# Arduino_ultrasonic_triac.net
KiCad netlist of a schematic drawn in EAGLE
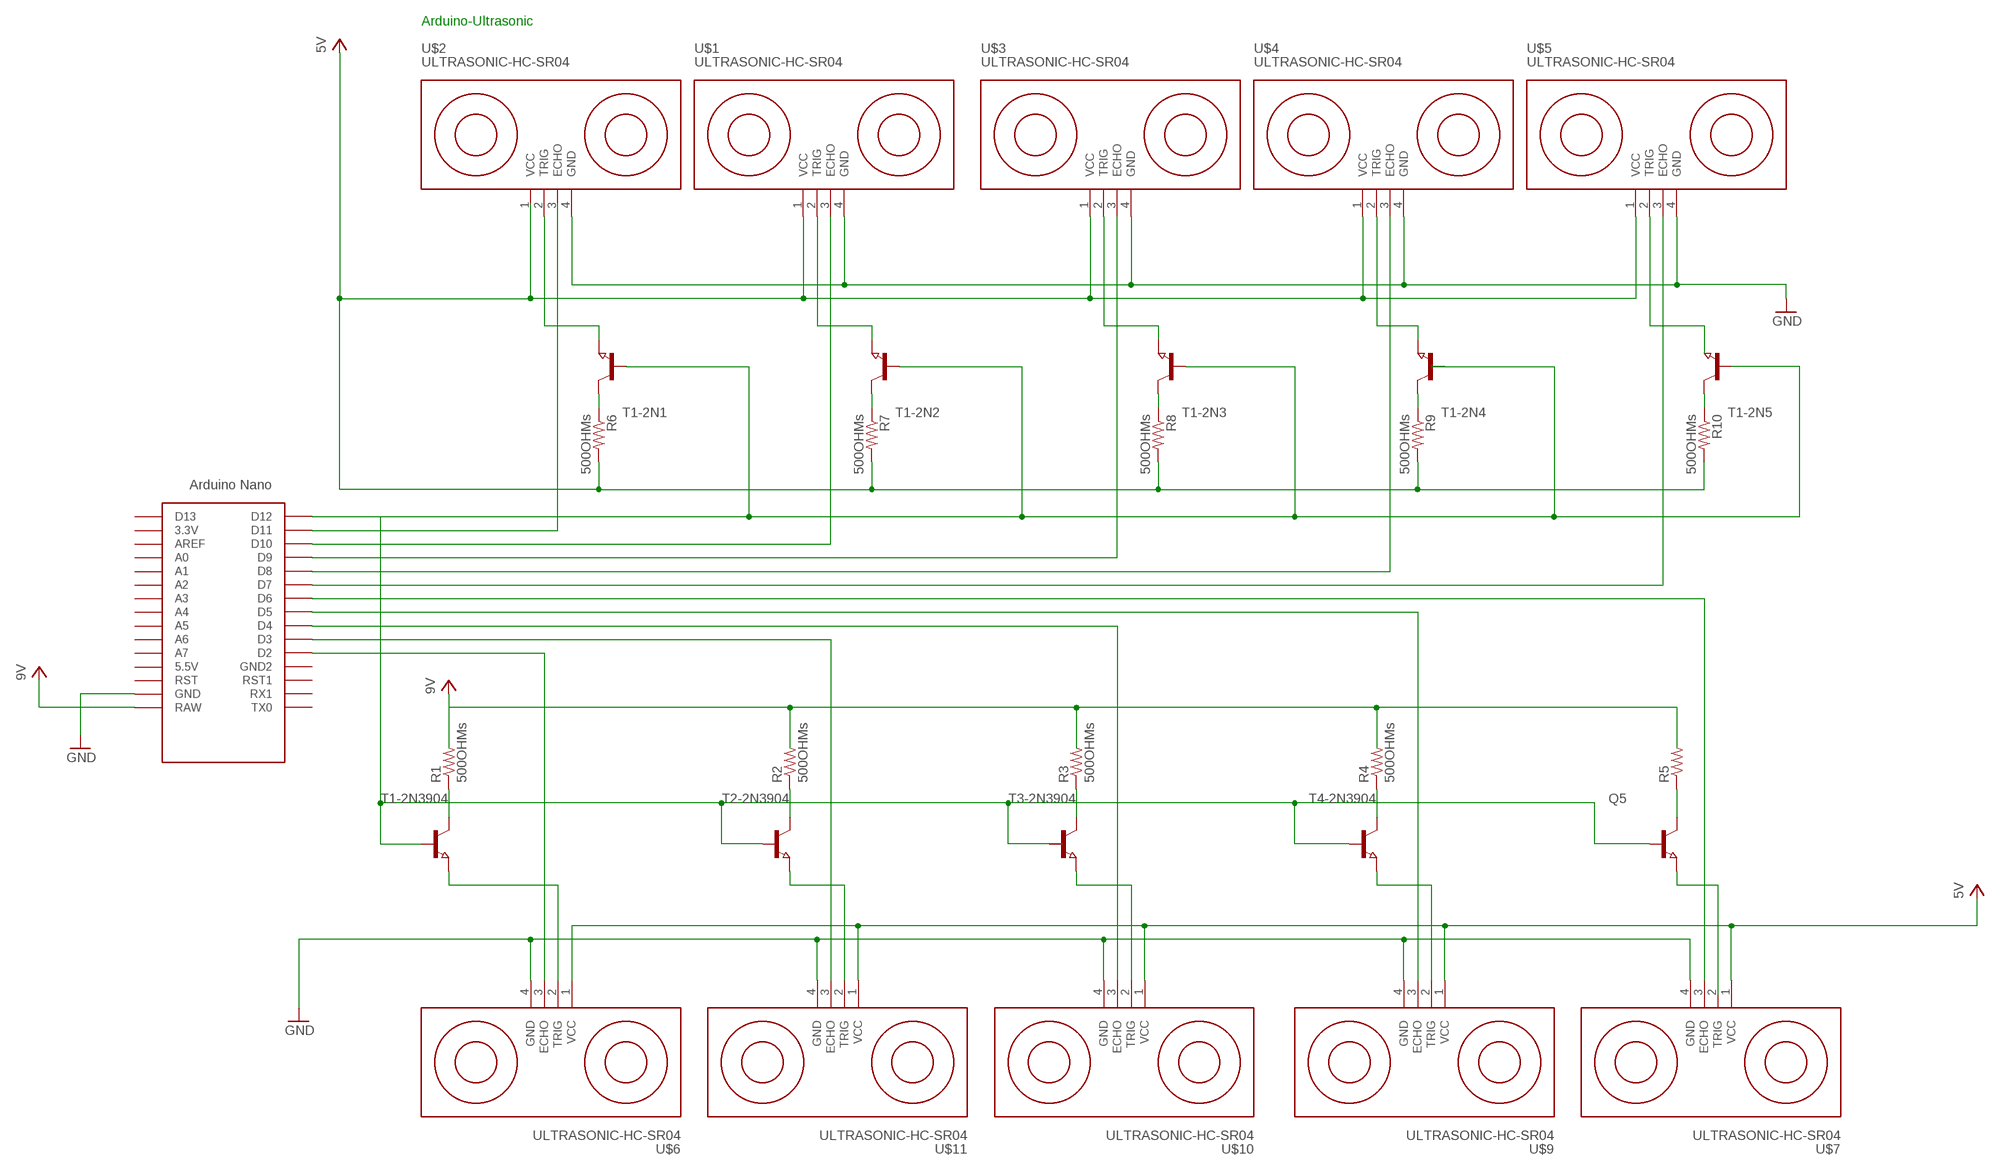
[diagram p0: schematic, sheet 1]

(export (version "E")
  (design (tool "Eeschema 10.0.6"))
  (components
    (comp (ref "Q5")
      (value "NPN-TRANSISTOR_SOT23")
      (footprint "eagle-import:SOT23")
      (libsource (lib "eagle-import") (part "NPN-TRANSISTOR_SOT23"))
    )
    (comp (ref "R1")
      (value "500OHMs")
      (footprint "eagle-import:0204V")
      (libsource (lib "eagle-import") (part "R-US_0204/2V"))
    )
    (comp (ref "R2")
      (value "500OHMs")
      (footprint "eagle-import:0204V")
      (libsource (lib "eagle-import") (part "R-US_0204/2V"))
    )
    (comp (ref "R3")
      (value "500OHMs")
      (footprint "eagle-import:0204V")
      (libsource (lib "eagle-import") (part "R-US_0204/2V"))
    )
    (comp (ref "R4")
      (value "500OHMs")
      (footprint "eagle-import:0204V")
      (libsource (lib "eagle-import") (part "R-US_0204/2V"))
    )
    (comp (ref "R5")
      (value "R-US_0204/2V")
      (footprint "eagle-import:0204V")
      (libsource (lib "eagle-import") (part "R-US_0204/2V"))
    )
    (comp (ref "R6")
      (value "500OHMs")
      (footprint "eagle-import:0204V")
      (libsource (lib "eagle-import") (part "R-US_0204/2V"))
    )
    (comp (ref "R7")
      (value "500OHMs")
      (footprint "eagle-import:0204V")
      (libsource (lib "eagle-import") (part "R-US_0204/2V"))
    )
    (comp (ref "R8")
      (value "500OHMs")
      (footprint "eagle-import:0204V")
      (libsource (lib "eagle-import") (part "R-US_0204/2V"))
    )
    (comp (ref "R9")
      (value "500OHMs")
      (footprint "eagle-import:0204V")
      (libsource (lib "eagle-import") (part "R-US_0204/2V"))
    )
    (comp (ref "R10")
      (value "500OHMs")
      (footprint "eagle-import:0204V")
      (libsource (lib "eagle-import") (part "R-US_0204/2V"))
    )
    (comp (ref "T1-2N1")
      (value "NPN-TRANSISTOR_SOT23")
      (footprint "eagle-import:SOT23")
      (libsource (lib "eagle-import") (part "NPN-TRANSISTOR_SOT23"))
    )
    (comp (ref "T1-2N2")
      (value "NPN-TRANSISTOR_SOT23")
      (footprint "eagle-import:SOT23")
      (libsource (lib "eagle-import") (part "NPN-TRANSISTOR_SOT23"))
    )
    (comp (ref "T1-2N3")
      (value "NPN-TRANSISTOR_SOT23")
      (footprint "eagle-import:SOT23")
      (libsource (lib "eagle-import") (part "NPN-TRANSISTOR_SOT23"))
    )
    (comp (ref "T1-2N4")
      (value "NPN-TRANSISTOR_SOT23")
      (footprint "eagle-import:SOT23")
      (libsource (lib "eagle-import") (part "NPN-TRANSISTOR_SOT23"))
    )
    (comp (ref "T1-2N5")
      (value "NPN-TRANSISTOR_SOT23")
      (footprint "eagle-import:SOT23")
      (libsource (lib "eagle-import") (part "NPN-TRANSISTOR_SOT23"))
    )
    (comp (ref "T1-2N3904")
      (value "NPN-TRANSISTOR_SOT23")
      (footprint "eagle-import:SOT23")
      (libsource (lib "eagle-import") (part "NPN-TRANSISTOR_SOT23"))
    )
    (comp (ref "T2-2N3904")
      (value "NPN-TRANSISTOR_SOT23")
      (footprint "eagle-import:SOT23")
      (libsource (lib "eagle-import") (part "NPN-TRANSISTOR_SOT23"))
    )
    (comp (ref "T3-2N3904")
      (value "NPN-TRANSISTOR_SOT23")
      (footprint "eagle-import:SOT23")
      (libsource (lib "eagle-import") (part "NPN-TRANSISTOR_SOT23"))
    )
    (comp (ref "T4-2N3904")
      (value "NPN-TRANSISTOR_SOT23")
      (footprint "eagle-import:SOT23")
      (libsource (lib "eagle-import") (part "NPN-TRANSISTOR_SOT23"))
    )
    (comp (ref "U$1")
      (value "ULTRASONIC-HC-SR04")
      (footprint "eagle-import:ULTRASONIC-HC-SR04")
      (libsource (lib "eagle-import") (part "ULTRASONIC-HC-SR04"))
    )
    (comp (ref "U$2")
      (value "ULTRASONIC-HC-SR04")
      (footprint "eagle-import:ULTRASONIC-HC-SR04")
      (libsource (lib "eagle-import") (part "ULTRASONIC-HC-SR04"))
    )
    (comp (ref "U$3")
      (value "ULTRASONIC-HC-SR04")
      (footprint "eagle-import:ULTRASONIC-HC-SR04")
      (libsource (lib "eagle-import") (part "ULTRASONIC-HC-SR04"))
    )
    (comp (ref "U$4")
      (value "ULTRASONIC-HC-SR04")
      (footprint "eagle-import:ULTRASONIC-HC-SR04")
      (libsource (lib "eagle-import") (part "ULTRASONIC-HC-SR04"))
    )
    (comp (ref "U$5")
      (value "ULTRASONIC-HC-SR04")
      (footprint "eagle-import:ULTRASONIC-HC-SR04")
      (libsource (lib "eagle-import") (part "ULTRASONIC-HC-SR04"))
    )
    (comp (ref "U$6")
      (value "ULTRASONIC-HC-SR04")
      (footprint "eagle-import:ULTRASONIC-HC-SR04")
      (libsource (lib "eagle-import") (part "ULTRASONIC-HC-SR04"))
    )
    (comp (ref "U$7")
      (value "ULTRASONIC-HC-SR04")
      (footprint "eagle-import:ULTRASONIC-HC-SR04")
      (libsource (lib "eagle-import") (part "ULTRASONIC-HC-SR04"))
    )
    (comp (ref "U$9")
      (value "ULTRASONIC-HC-SR04")
      (footprint "eagle-import:ULTRASONIC-HC-SR04")
      (libsource (lib "eagle-import") (part "ULTRASONIC-HC-SR04"))
    )
    (comp (ref "U$10")
      (value "ULTRASONIC-HC-SR04")
      (footprint "eagle-import:ULTRASONIC-HC-SR04")
      (libsource (lib "eagle-import") (part "ULTRASONIC-HC-SR04"))
    )
    (comp (ref "U$11")
      (value "ULTRASONIC-HC-SR04")
      (footprint "eagle-import:ULTRASONIC-HC-SR04")
      (libsource (lib "eagle-import") (part "ULTRASONIC-HC-SR04"))
    )
    (comp (ref "U$12")
      (value "NANO")
      (footprint "eagle-import:NANO")
      (libsource (lib "eagle-import") (part "NANO"))
    )
  )
  (nets
    (net (code "1") (name "5V") (class "Default")
      (node (ref "Q5") (pin "1") (pinfunction "B_1") (pintype "passive"))
      (node (ref "R1") (pin "1") (pinfunction "1_1") (pintype "passive"))
      (node (ref "R10") (pin "2") (pinfunction "2_2") (pintype "passive"))
      (node (ref "R6") (pin "2") (pinfunction "2_2") (pintype "passive"))
      (node (ref "R7") (pin "2") (pinfunction "2_2") (pintype "passive"))
      (node (ref "R8") (pin "2") (pinfunction "2_2") (pintype "passive"))
      (node (ref "R9") (pin "2") (pinfunction "2_2") (pintype "passive"))
      (node (ref "T1-2N1") (pin "1") (pinfunction "B_1") (pintype "passive"))
      (node (ref "T1-2N2") (pin "1") (pinfunction "B_1") (pintype "passive"))
      (node (ref "T1-2N3") (pin "1") (pinfunction "B_1") (pintype "passive"))
      (node (ref "T1-2N3904") (pin "1") (pinfunction "B_1") (pintype "passive"))
      (node (ref "T1-2N3904") (pin "3") (pinfunction "C_3") (pintype "passive"))
      (node (ref "T1-2N5") (pin "1") (pinfunction "B_1") (pintype "passive"))
      (node (ref "T2-2N3904") (pin "1") (pinfunction "B_1") (pintype "passive"))
      (node (ref "T4-2N3904") (pin "1") (pinfunction "B_1") (pintype "passive"))
      (node (ref "U$1") (pin "1") (pinfunction "VCC_1") (pintype "power_in"))
      (node (ref "U$10") (pin "1") (pinfunction "VCC_1") (pintype "power_in"))
      (node (ref "U$11") (pin "1") (pinfunction "VCC_1") (pintype "power_in"))
      (node (ref "U$12") (pin "D12") (pinfunction "D12_D12") (pintype "bidirectional"))
      (node (ref "U$12") (pin "RAW") (pinfunction "RAW_RAW") (pintype "bidirectional"))
      (node (ref "U$2") (pin "1") (pinfunction "VCC_1") (pintype "power_in"))
      (node (ref "U$3") (pin "1") (pinfunction "VCC_1") (pintype "power_in"))
      (node (ref "U$4") (pin "1") (pinfunction "VCC_1") (pintype "power_in"))
      (node (ref "U$5") (pin "1") (pinfunction "VCC_1") (pintype "power_in"))
      (node (ref "U$6") (pin "1") (pinfunction "VCC_1") (pintype "power_in"))
      (node (ref "U$7") (pin "1") (pinfunction "VCC_1") (pintype "power_in"))
      (node (ref "U$9") (pin "1") (pinfunction "VCC_1") (pintype "power_in"))
    )
    (net (code "2") (name "GND") (class "Default")
      (node (ref "U$1") (pin "4") (pinfunction "GND_4") (pintype "power_in"))
      (node (ref "U$10") (pin "4") (pinfunction "GND_4") (pintype "power_in"))
      (node (ref "U$11") (pin "4") (pinfunction "GND_4") (pintype "power_in"))
      (node (ref "U$12") (pin "GND") (pinfunction "GND_GND") (pintype "bidirectional"))
      (node (ref "U$2") (pin "4") (pinfunction "GND_4") (pintype "power_in"))
      (node (ref "U$3") (pin "4") (pinfunction "GND_4") (pintype "power_in"))
      (node (ref "U$4") (pin "4") (pinfunction "GND_4") (pintype "power_in"))
      (node (ref "U$5") (pin "4") (pinfunction "GND_4") (pintype "power_in"))
      (node (ref "U$6") (pin "4") (pinfunction "GND_4") (pintype "power_in"))
      (node (ref "U$7") (pin "4") (pinfunction "GND_4") (pintype "power_in"))
      (node (ref "U$9") (pin "4") (pinfunction "GND_4") (pintype "power_in"))
    )
    (net (code "3") (name "Net-(Q5-C)") (class "Default")
      (node (ref "Q5") (pin "3") (pinfunction "C_3") (pintype "passive"))
      (node (ref "R5") (pin "1") (pinfunction "1_1") (pintype "passive"))
    )
    (net (code "4") (name "Net-(T1-2N1-C)") (class "Default")
      (node (ref "R6") (pin "1") (pinfunction "1_1") (pintype "passive"))
      (node (ref "T1-2N1") (pin "3") (pinfunction "C_3") (pintype "passive"))
    )
    (net (code "5") (name "Net-(T1-2N1-E)") (class "Default")
      (node (ref "T1-2N1") (pin "2") (pinfunction "E_2") (pintype "passive"))
      (node (ref "U$2") (pin "2") (pinfunction "TRIG_2") (pintype "input"))
    )
    (net (code "6") (name "Net-(T1-2N2-C)") (class "Default")
      (node (ref "R7") (pin "1") (pinfunction "1_1") (pintype "passive"))
      (node (ref "T1-2N2") (pin "3") (pinfunction "C_3") (pintype "passive"))
    )
    (net (code "7") (name "Net-(T1-2N2-E)") (class "Default")
      (node (ref "T1-2N2") (pin "2") (pinfunction "E_2") (pintype "passive"))
      (node (ref "U$1") (pin "2") (pinfunction "TRIG_2") (pintype "input"))
    )
    (net (code "8") (name "Net-(T1-2N3-C)") (class "Default")
      (node (ref "R8") (pin "1") (pinfunction "1_1") (pintype "passive"))
      (node (ref "T1-2N3") (pin "3") (pinfunction "C_3") (pintype "passive"))
    )
    (net (code "9") (name "Net-(T1-2N3-E)") (class "Default")
      (node (ref "T1-2N3") (pin "2") (pinfunction "E_2") (pintype "passive"))
      (node (ref "U$3") (pin "2") (pinfunction "TRIG_2") (pintype "input"))
    )
    (net (code "10") (name "Net-(T1-2N4-C)") (class "Default")
      (node (ref "R9") (pin "1") (pinfunction "1_1") (pintype "passive"))
      (node (ref "T1-2N4") (pin "3") (pinfunction "C_3") (pintype "passive"))
    )
    (net (code "11") (name "Net-(T1-2N4-E)") (class "Default")
      (node (ref "T1-2N4") (pin "2") (pinfunction "E_2") (pintype "passive"))
      (node (ref "U$4") (pin "2") (pinfunction "TRIG_2") (pintype "input"))
    )
    (net (code "12") (name "Net-(T1-2N5-C)") (class "Default")
      (node (ref "R10") (pin "1") (pinfunction "1_1") (pintype "passive"))
      (node (ref "T1-2N5") (pin "3") (pinfunction "C_3") (pintype "passive"))
    )
    (net (code "13") (name "Net-(T1-2N3904-E)") (class "Default")
      (node (ref "T1-2N3904") (pin "2") (pinfunction "E_2") (pintype "passive"))
      (node (ref "U$6") (pin "2") (pinfunction "TRIG_2") (pintype "input"))
    )
    (net (code "14") (name "Net-(T2-2N3904-C)") (class "Default")
      (node (ref "R2") (pin "1") (pinfunction "1_1") (pintype "passive"))
      (node (ref "T2-2N3904") (pin "3") (pinfunction "C_3") (pintype "passive"))
    )
    (net (code "15") (name "Net-(T2-2N3904-E)") (class "Default")
      (node (ref "T2-2N3904") (pin "2") (pinfunction "E_2") (pintype "passive"))
      (node (ref "U$11") (pin "2") (pinfunction "TRIG_2") (pintype "input"))
    )
    (net (code "16") (name "Net-(T3-2N3904-C)") (class "Default")
      (node (ref "R3") (pin "1") (pinfunction "1_1") (pintype "passive"))
      (node (ref "T3-2N3904") (pin "3") (pinfunction "C_3") (pintype "passive"))
    )
    (net (code "17") (name "Net-(T3-2N3904-E)") (class "Default")
      (node (ref "T3-2N3904") (pin "2") (pinfunction "E_2") (pintype "passive"))
      (node (ref "U$10") (pin "2") (pinfunction "TRIG_2") (pintype "input"))
    )
    (net (code "18") (name "Net-(T4-2N3904-C)") (class "Default")
      (node (ref "R4") (pin "1") (pinfunction "1_1") (pintype "passive"))
      (node (ref "T4-2N3904") (pin "3") (pinfunction "C_3") (pintype "passive"))
    )
    (net (code "19") (name "Net-(T4-2N3904-E)") (class "Default")
      (node (ref "T4-2N3904") (pin "2") (pinfunction "E_2") (pintype "passive"))
      (node (ref "U$9") (pin "2") (pinfunction "TRIG_2") (pintype "input"))
    )
    (net (code "20") (name "Net-(U$1-ECHO)") (class "Default")
      (node (ref "U$1") (pin "3") (pinfunction "ECHO_3") (pintype "output"))
      (node (ref "U$12") (pin "D10") (pinfunction "D10_D10") (pintype "bidirectional"))
    )
    (net (code "21") (name "Net-(U$2-ECHO)") (class "Default")
      (node (ref "U$12") (pin "D11") (pinfunction "D11_D11") (pintype "bidirectional"))
      (node (ref "U$2") (pin "3") (pinfunction "ECHO_3") (pintype "output"))
    )
    (net (code "22") (name "Net-(U$3-ECHO)") (class "Default")
      (node (ref "U$12") (pin "D9") (pinfunction "D9_D9") (pintype "bidirectional"))
      (node (ref "U$3") (pin "3") (pinfunction "ECHO_3") (pintype "output"))
    )
    (net (code "23") (name "Net-(U$4-ECHO)") (class "Default")
      (node (ref "U$12") (pin "D8") (pinfunction "D8_D8") (pintype "bidirectional"))
      (node (ref "U$4") (pin "3") (pinfunction "ECHO_3") (pintype "output"))
    )
    (net (code "24") (name "Net-(U$5-ECHO)") (class "Default")
      (node (ref "U$12") (pin "D7") (pinfunction "D7_D7") (pintype "bidirectional"))
      (node (ref "U$5") (pin "3") (pinfunction "ECHO_3") (pintype "output"))
    )
    (net (code "25") (name "Net-(U$6-ECHO)") (class "Default")
      (node (ref "U$12") (pin "D2") (pinfunction "D2_D2") (pintype "bidirectional"))
      (node (ref "U$6") (pin "3") (pinfunction "ECHO_3") (pintype "output"))
    )
    (net (code "26") (name "Net-(U$7-ECHO)") (class "Default")
      (node (ref "U$12") (pin "D6") (pinfunction "D6_D6") (pintype "bidirectional"))
      (node (ref "U$7") (pin "3") (pinfunction "ECHO_3") (pintype "output"))
    )
    (net (code "27") (name "Net-(U$9-ECHO)") (class "Default")
      (node (ref "U$12") (pin "D5") (pinfunction "D5_D5") (pintype "bidirectional"))
      (node (ref "U$9") (pin "3") (pinfunction "ECHO_3") (pintype "output"))
    )
    (net (code "28") (name "Net-(U$10-ECHO)") (class "Default")
      (node (ref "U$10") (pin "3") (pinfunction "ECHO_3") (pintype "output"))
      (node (ref "U$12") (pin "D4") (pinfunction "D4_D4") (pintype "bidirectional"))
    )
    (net (code "29") (name "Net-(U$11-ECHO)") (class "Default")
      (node (ref "U$11") (pin "3") (pinfunction "ECHO_3") (pintype "output"))
      (node (ref "U$12") (pin "D3") (pinfunction "D3_D3") (pintype "bidirectional"))
    )
    (net (code "30") (name "unconnected-(Q5-E-Pad2)") (class "Default")
      (node (ref "Q5") (pin "2") (pinfunction "E_2") (pintype "passive"))
    )
    (net (code "31") (name "unconnected-(R1-Pad2)") (class "Default")
      (node (ref "R1") (pin "2") (pinfunction "2_2") (pintype "passive"))
    )
    (net (code "32") (name "unconnected-(R2-Pad2)") (class "Default")
      (node (ref "R2") (pin "2") (pinfunction "2_2") (pintype "passive"))
    )
    (net (code "33") (name "unconnected-(R3-Pad2)") (class "Default")
      (node (ref "R3") (pin "2") (pinfunction "2_2") (pintype "passive"))
    )
    (net (code "34") (name "unconnected-(R4-Pad2)") (class "Default")
      (node (ref "R4") (pin "2") (pinfunction "2_2") (pintype "passive"))
    )
    (net (code "35") (name "unconnected-(R5-Pad2)") (class "Default")
      (node (ref "R5") (pin "2") (pinfunction "2_2") (pintype "passive"))
    )
    (net (code "36") (name "unconnected-(T1-2N4-B-Pad1)") (class "Default")
      (node (ref "T1-2N4") (pin "1") (pinfunction "B_1") (pintype "passive"))
    )
    (net (code "37") (name "unconnected-(T1-2N5-E-Pad2)") (class "Default")
      (node (ref "T1-2N5") (pin "2") (pinfunction "E_2") (pintype "passive"))
    )
    (net (code "38") (name "unconnected-(T3-2N3904-B-Pad1)") (class "Default")
      (node (ref "T3-2N3904") (pin "1") (pinfunction "B_1") (pintype "passive"))
    )
    (net (code "39") (name "unconnected-(U$5-TRIG-Pad2)") (class "Default")
      (node (ref "U$5") (pin "2") (pinfunction "TRIG_2") (pintype "input"))
    )
    (net (code "40") (name "unconnected-(U$7-TRIG-Pad2)") (class "Default")
      (node (ref "U$7") (pin "2") (pinfunction "TRIG_2") (pintype "input"))
    )
    (net (code "41") (name "unconnected-(U$12-5.5V-Pad5V)") (class "Default")
      (node (ref "U$12") (pin "5V") (pinfunction "5.5V_5V") (pintype "bidirectional"))
    )
    (net (code "42") (name "unconnected-(U$12-GND2-PadGND1)") (class "Default")
      (node (ref "U$12") (pin "GND1") (pinfunction "GND2_GND1") (pintype "bidirectional"))
    )
    (net (code "43") (name "unconnected-(U$12-Pad3.3V)") (class "Default")
      (node (ref "U$12") (pin "3.3V") (pinfunction "3.3V_3.3V") (pintype "bidirectional"))
    )
    (net (code "44") (name "unconnected-(U$12-PadA0)") (class "Default")
      (node (ref "U$12") (pin "A0") (pinfunction "A0_A0") (pintype "bidirectional"))
    )
    (net (code "45") (name "unconnected-(U$12-PadA1)") (class "Default")
      (node (ref "U$12") (pin "A1") (pinfunction "A1_A1") (pintype "bidirectional"))
    )
    (net (code "46") (name "unconnected-(U$12-PadA2)") (class "Default")
      (node (ref "U$12") (pin "A2") (pinfunction "A2_A2") (pintype "bidirectional"))
    )
    (net (code "47") (name "unconnected-(U$12-PadA3)") (class "Default")
      (node (ref "U$12") (pin "A3") (pinfunction "A3_A3") (pintype "bidirectional"))
    )
    (net (code "48") (name "unconnected-(U$12-PadA4)") (class "Default")
      (node (ref "U$12") (pin "A4") (pinfunction "A4_A4") (pintype "bidirectional"))
    )
    (net (code "49") (name "unconnected-(U$12-PadA5)") (class "Default")
      (node (ref "U$12") (pin "A5") (pinfunction "A5_A5") (pintype "bidirectional"))
    )
    (net (code "50") (name "unconnected-(U$12-PadA6)") (class "Default")
      (node (ref "U$12") (pin "A6") (pinfunction "A6_A6") (pintype "bidirectional"))
    )
    (net (code "51") (name "unconnected-(U$12-PadA7)") (class "Default")
      (node (ref "U$12") (pin "A7") (pinfunction "A7_A7") (pintype "bidirectional"))
    )
    (net (code "52") (name "unconnected-(U$12-PadAREF)") (class "Default")
      (node (ref "U$12") (pin "AREF") (pinfunction "AREF_AREF") (pintype "bidirectional"))
    )
    (net (code "53") (name "unconnected-(U$12-PadD13)") (class "Default")
      (node (ref "U$12") (pin "D13") (pinfunction "D13_D13") (pintype "bidirectional"))
    )
    (net (code "54") (name "unconnected-(U$12-PadICSP1)") (class "Default")
      (node (ref "U$12") (pin "ICSP1") (pinfunction "ICSP1_ICSP1") (pintype "bidirectional"))
    )
    (net (code "55") (name "unconnected-(U$12-PadICSP2)") (class "Default")
      (node (ref "U$12") (pin "ICSP2") (pinfunction "ICSP2_ICSP2") (pintype "bidirectional"))
    )
    (net (code "56") (name "unconnected-(U$12-PadICSP3)") (class "Default")
      (node (ref "U$12") (pin "ICSP3") (pinfunction "ICSP3_ICSP3") (pintype "bidirectional"))
    )
    (net (code "57") (name "unconnected-(U$12-PadICSP4)") (class "Default")
      (node (ref "U$12") (pin "ICSP4") (pinfunction "ICSP4_ICSP4") (pintype "bidirectional"))
    )
    (net (code "58") (name "unconnected-(U$12-PadICSP5)") (class "Default")
      (node (ref "U$12") (pin "ICSP5") (pinfunction "ICSP5_ICSP5") (pintype "bidirectional"))
    )
    (net (code "59") (name "unconnected-(U$12-PadICSP6)") (class "Default")
      (node (ref "U$12") (pin "ICSP6") (pinfunction "ICSP6_ICSP6") (pintype "bidirectional"))
    )
    (net (code "60") (name "unconnected-(U$12-PadRST)") (class "Default")
      (node (ref "U$12") (pin "RST") (pinfunction "RST_RST") (pintype "bidirectional"))
    )
    (net (code "61") (name "unconnected-(U$12-PadRST1)") (class "Default")
      (node (ref "U$12") (pin "RST1") (pinfunction "RST1_RST1") (pintype "bidirectional"))
    )
    (net (code "62") (name "unconnected-(U$12-PadRX1)") (class "Default")
      (node (ref "U$12") (pin "RX1") (pinfunction "RX1_RX1") (pintype "bidirectional"))
    )
    (net (code "63") (name "unconnected-(U$12-PadTX0)") (class "Default")
      (node (ref "U$12") (pin "TX0") (pinfunction "TX0_TX0") (pintype "bidirectional"))
    )
  )
)
